# board.net
KiCad netlist of a schematic drawn in EAGLE
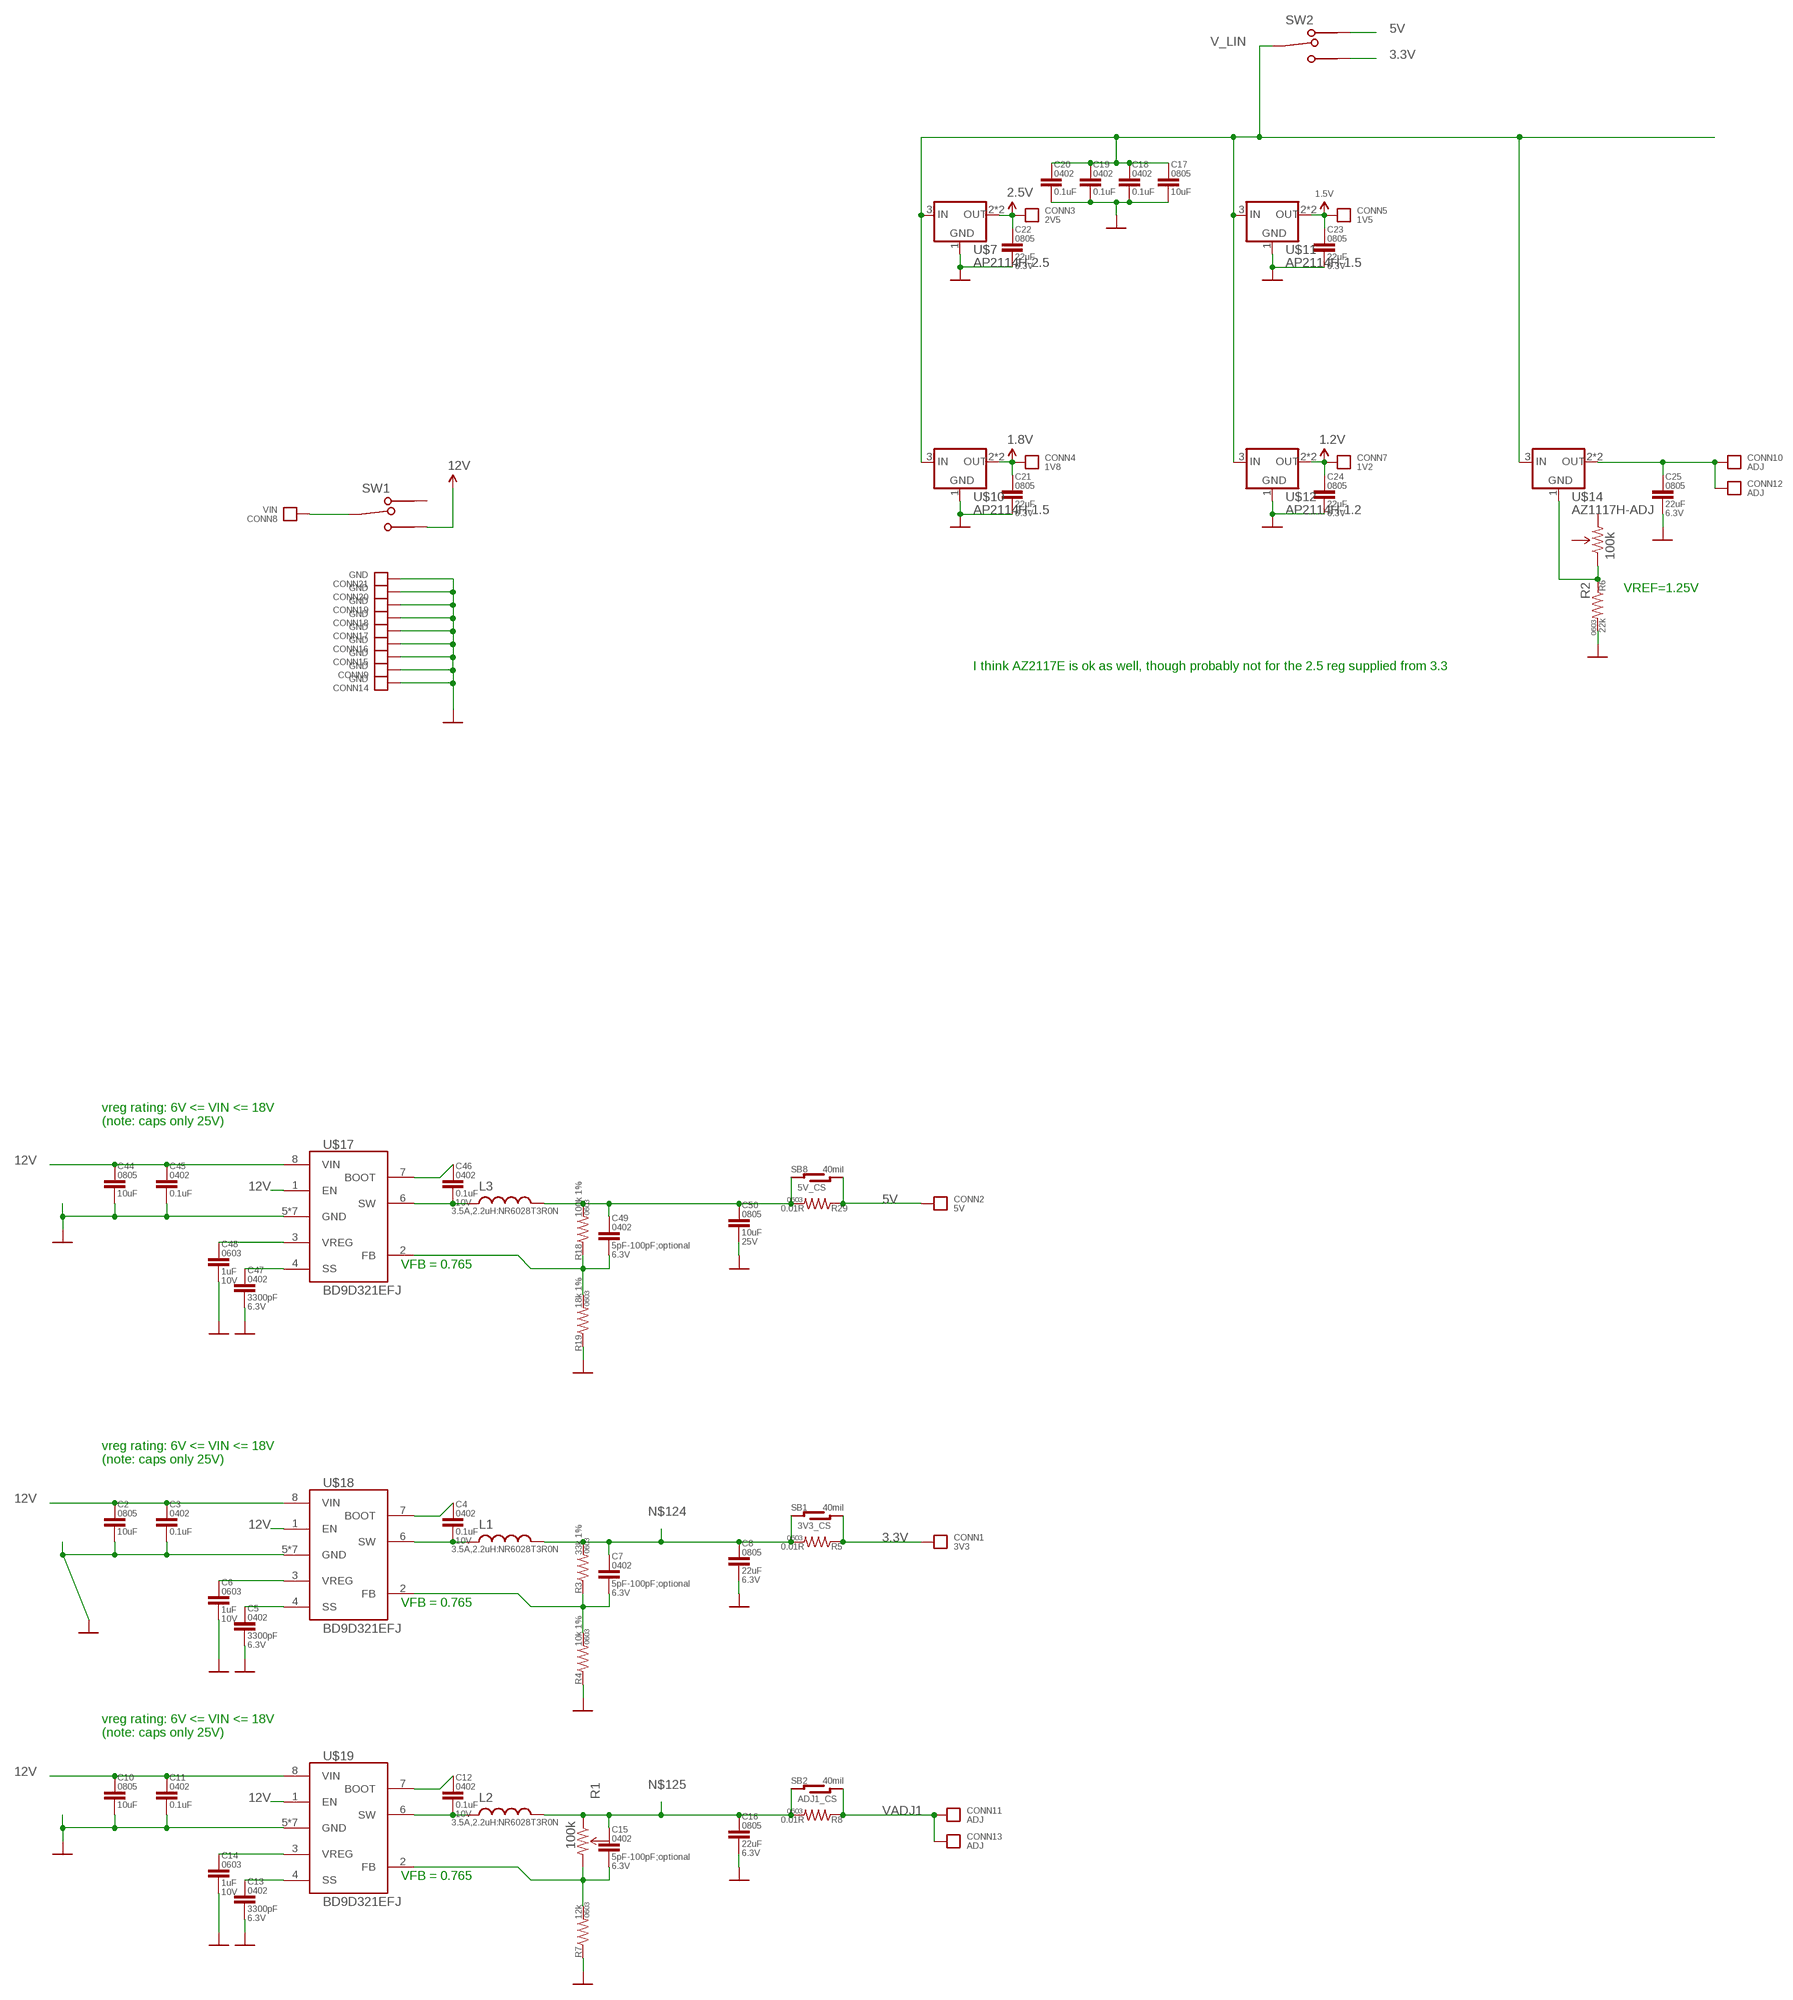
[diagram p0: schematic, sheet 1]

(export (version "E")
  (design (tool "Eeschema 10.0.6"))
  (components
    (comp (ref "C2")
      (value "10uF")
      (footprint "eagle-import:0805-CAP")
      (fields (field (name "VOLTAGE") "6.3V") (field (name "VOLTAGE_1") "25V"))
      (libsource (lib "eagle-import") (part "CAP0805"))
    )
    (comp (ref "C3")
      (value "0.1uF")
      (footprint "eagle-import:0402-CAP")
      (fields (field (name "VOLTAGE") "6.3V") (field (name "VOLTAGE_1") "25V"))
      (libsource (lib "eagle-import") (part "CAP0402-CAP"))
    )
    (comp (ref "C4")
      (value "0.1uF")
      (footprint "eagle-import:0402-CAP")
      (fields (field (name "VOLTAGE") "6.3V") (field (name "VOLTAGE_1") "10V"))
      (libsource (lib "eagle-import") (part "CAP0402-CAP"))
    )
    (comp (ref "C5")
      (value "3300pF")
      (footprint "eagle-import:0402-CAP")
      (fields (field (name "VOLTAGE") "6.3V"))
      (libsource (lib "eagle-import") (part "CAP0402-CAP"))
    )
    (comp (ref "C6")
      (value "1uF")
      (footprint "eagle-import:0603-CAP")
      (fields (field (name "VOLTAGE") "6.3V") (field (name "VOLTAGE_1") "10V"))
      (libsource (lib "eagle-import") (part "CAP0603"))
    )
    (comp (ref "C7")
      (value "5pF-100pF;optional")
      (footprint "eagle-import:0402-CAP")
      (fields (field (name "VOLTAGE") "6.3V"))
      (libsource (lib "eagle-import") (part "CAP0402-CAP"))
    )
    (comp (ref "C8")
      (value "22uF")
      (footprint "eagle-import:0805-CAP")
      (fields (field (name "VOLTAGE") "6.3V"))
      (libsource (lib "eagle-import") (part "CAP0805"))
    )
    (comp (ref "C10")
      (value "10uF")
      (footprint "eagle-import:0805-CAP")
      (fields (field (name "VOLTAGE") "6.3V") (field (name "VOLTAGE_1") "25V"))
      (libsource (lib "eagle-import") (part "CAP0805"))
    )
    (comp (ref "C11")
      (value "0.1uF")
      (footprint "eagle-import:0402-CAP")
      (fields (field (name "VOLTAGE") "6.3V") (field (name "VOLTAGE_1") "25V"))
      (libsource (lib "eagle-import") (part "CAP0402-CAP"))
    )
    (comp (ref "C12")
      (value "0.1uF")
      (footprint "eagle-import:0402-CAP")
      (fields (field (name "VOLTAGE") "6.3V") (field (name "VOLTAGE_1") "10V"))
      (libsource (lib "eagle-import") (part "CAP0402-CAP"))
    )
    (comp (ref "C13")
      (value "3300pF")
      (footprint "eagle-import:0402-CAP")
      (fields (field (name "VOLTAGE") "6.3V"))
      (libsource (lib "eagle-import") (part "CAP0402-CAP"))
    )
    (comp (ref "C14")
      (value "1uF")
      (footprint "eagle-import:0603-CAP")
      (fields (field (name "VOLTAGE") "6.3V") (field (name "VOLTAGE_1") "10V"))
      (libsource (lib "eagle-import") (part "CAP0603"))
    )
    (comp (ref "C15")
      (value "5pF-100pF;optional")
      (footprint "eagle-import:0402-CAP")
      (fields (field (name "VOLTAGE") "6.3V"))
      (libsource (lib "eagle-import") (part "CAP0402-CAP"))
    )
    (comp (ref "C16")
      (value "22uF")
      (footprint "eagle-import:0805-CAP")
      (fields (field (name "VOLTAGE") "6.3V"))
      (libsource (lib "eagle-import") (part "CAP0805"))
    )
    (comp (ref "C17")
      (value "10uF")
      (footprint "eagle-import:0805-CAP")
      (fields (field (name "VOLTAGE") "6.3V") (field (name "VOLTAGE_1") "25V"))
      (libsource (lib "eagle-import") (part "CAP0805"))
    )
    (comp (ref "C18")
      (value "0.1uF")
      (footprint "eagle-import:0402-CAP")
      (fields (field (name "VOLTAGE") "6.3V") (field (name "VOLTAGE_1") "25V"))
      (libsource (lib "eagle-import") (part "CAP0402-CAP"))
    )
    (comp (ref "C19")
      (value "0.1uF")
      (footprint "eagle-import:0402-CAP")
      (fields (field (name "VOLTAGE") "6.3V") (field (name "VOLTAGE_1") "25V"))
      (libsource (lib "eagle-import") (part "CAP0402-CAP"))
    )
    (comp (ref "C20")
      (value "0.1uF")
      (footprint "eagle-import:0402-CAP")
      (fields (field (name "VOLTAGE") "6.3V") (field (name "VOLTAGE_1") "25V"))
      (libsource (lib "eagle-import") (part "CAP0402-CAP"))
    )
    (comp (ref "C21")
      (value "22uF")
      (footprint "eagle-import:0805-CAP")
      (fields (field (name "VOLTAGE") "6.3V"))
      (libsource (lib "eagle-import") (part "CAP0805"))
    )
    (comp (ref "C22")
      (value "22uF")
      (footprint "eagle-import:0805-CAP")
      (fields (field (name "VOLTAGE") "6.3V"))
      (libsource (lib "eagle-import") (part "CAP0805"))
    )
    (comp (ref "C23")
      (value "22uF")
      (footprint "eagle-import:0805-CAP")
      (fields (field (name "VOLTAGE") "6.3V"))
      (libsource (lib "eagle-import") (part "CAP0805"))
    )
    (comp (ref "C24")
      (value "22uF")
      (footprint "eagle-import:0805-CAP")
      (fields (field (name "VOLTAGE") "6.3V"))
      (libsource (lib "eagle-import") (part "CAP0805"))
    )
    (comp (ref "C25")
      (value "22uF")
      (footprint "eagle-import:0805-CAP")
      (fields (field (name "VOLTAGE") "6.3V"))
      (libsource (lib "eagle-import") (part "CAP0805"))
    )
    (comp (ref "C44")
      (value "10uF")
      (footprint "eagle-import:0805-CAP")
      (fields (field (name "VOLTAGE") "6.3V") (field (name "VOLTAGE_1") "25V"))
      (libsource (lib "eagle-import") (part "CAP0805"))
    )
    (comp (ref "C45")
      (value "0.1uF")
      (footprint "eagle-import:0402-CAP")
      (fields (field (name "VOLTAGE") "6.3V") (field (name "VOLTAGE_1") "25V"))
      (libsource (lib "eagle-import") (part "CAP0402-CAP"))
    )
    (comp (ref "C46")
      (value "0.1uF")
      (footprint "eagle-import:0402-CAP")
      (fields (field (name "VOLTAGE") "6.3V") (field (name "VOLTAGE_1") "10V"))
      (libsource (lib "eagle-import") (part "CAP0402-CAP"))
    )
    (comp (ref "C47")
      (value "3300pF")
      (footprint "eagle-import:0402-CAP")
      (fields (field (name "VOLTAGE") "6.3V"))
      (libsource (lib "eagle-import") (part "CAP0402-CAP"))
    )
    (comp (ref "C48")
      (value "1uF")
      (footprint "eagle-import:0603-CAP")
      (fields (field (name "VOLTAGE") "6.3V") (field (name "VOLTAGE_1") "10V"))
      (libsource (lib "eagle-import") (part "CAP0603"))
    )
    (comp (ref "C49")
      (value "5pF-100pF;optional")
      (footprint "eagle-import:0402-CAP")
      (fields (field (name "VOLTAGE") "6.3V"))
      (libsource (lib "eagle-import") (part "CAP0402-CAP"))
    )
    (comp (ref "C50")
      (value "10uF")
      (footprint "eagle-import:0805-CAP")
      (fields (field (name "VOLTAGE") "6.3V") (field (name "VOLTAGE_1") "25V"))
      (libsource (lib "eagle-import") (part "CAP0805"))
    )
    (comp (ref "CONN1")
      (value "3V3")
      (footprint "eagle-import:HOLE_22AWG")
      (libsource (lib "eagle-import") (part "CONNECTOR22AWG"))
    )
    (comp (ref "CONN2")
      (value "5V")
      (footprint "eagle-import:HOLE_22AWG")
      (libsource (lib "eagle-import") (part "CONNECTOR22AWG"))
    )
    (comp (ref "CONN3")
      (value "2V5")
      (footprint "eagle-import:HOLE_22AWG")
      (libsource (lib "eagle-import") (part "CONNECTOR22AWG"))
    )
    (comp (ref "CONN4")
      (value "1V8")
      (footprint "eagle-import:HOLE_22AWG")
      (libsource (lib "eagle-import") (part "CONNECTOR22AWG"))
    )
    (comp (ref "CONN5")
      (value "1V5")
      (footprint "eagle-import:HOLE_22AWG")
      (libsource (lib "eagle-import") (part "CONNECTOR22AWG"))
    )
    (comp (ref "CONN7")
      (value "1V2")
      (footprint "eagle-import:HOLE_22AWG")
      (libsource (lib "eagle-import") (part "CONNECTOR22AWG"))
    )
    (comp (ref "CONN8")
      (value "VIN")
      (footprint "eagle-import:HOLE_22AWG")
      (libsource (lib "eagle-import") (part "CONNECTOR22AWG"))
    )
    (comp (ref "CONN9")
      (value "GND")
      (footprint "eagle-import:HOLE_22AWG")
      (libsource (lib "eagle-import") (part "CONNECTOR22AWG"))
    )
    (comp (ref "CONN10")
      (value "ADJ")
      (footprint "eagle-import:HOLE_22AWG")
      (libsource (lib "eagle-import") (part "CONNECTOR22AWG"))
    )
    (comp (ref "CONN11")
      (value "ADJ")
      (footprint "eagle-import:HOLE_22AWG")
      (libsource (lib "eagle-import") (part "CONNECTOR22AWG"))
    )
    (comp (ref "CONN12")
      (value "ADJ")
      (footprint "eagle-import:HOLE_28AWG")
      (libsource (lib "eagle-import") (part "CONNECTOR28AWG"))
    )
    (comp (ref "CONN13")
      (value "ADJ")
      (footprint "eagle-import:HOLE_28AWG")
      (libsource (lib "eagle-import") (part "CONNECTOR28AWG"))
    )
    (comp (ref "CONN14")
      (value "GND")
      (footprint "eagle-import:HOLE_22AWG")
      (libsource (lib "eagle-import") (part "CONNECTOR22AWG"))
    )
    (comp (ref "CONN15")
      (value "GND")
      (footprint "eagle-import:HOLE_22AWG")
      (libsource (lib "eagle-import") (part "CONNECTOR22AWG"))
    )
    (comp (ref "CONN16")
      (value "GND")
      (footprint "eagle-import:HOLE_22AWG")
      (libsource (lib "eagle-import") (part "CONNECTOR22AWG"))
    )
    (comp (ref "CONN17")
      (value "GND")
      (footprint "eagle-import:HOLE_22AWG")
      (libsource (lib "eagle-import") (part "CONNECTOR22AWG"))
    )
    (comp (ref "CONN18")
      (value "GND")
      (footprint "eagle-import:HOLE_22AWG")
      (libsource (lib "eagle-import") (part "CONNECTOR22AWG"))
    )
    (comp (ref "CONN19")
      (value "GND")
      (footprint "eagle-import:HOLE_22AWG")
      (libsource (lib "eagle-import") (part "CONNECTOR22AWG"))
    )
    (comp (ref "CONN20")
      (value "GND")
      (footprint "eagle-import:HOLE_22AWG")
      (libsource (lib "eagle-import") (part "CONNECTOR22AWG"))
    )
    (comp (ref "CONN21")
      (value "GND")
      (footprint "eagle-import:HOLE_22AWG")
      (libsource (lib "eagle-import") (part "CONNECTOR22AWG"))
    )
    (comp (ref "L1")
      (value "3.5A,2.2uH:NR6028T3R0N")
      (footprint "eagle-import:NR60XX")
      (libsource (lib "eagle-import") (part "INDUCTORNR60XX"))
    )
    (comp (ref "L2")
      (value "3.5A,2.2uH:NR6028T3R0N")
      (footprint "eagle-import:NR60XX")
      (libsource (lib "eagle-import") (part "INDUCTORNR60XX"))
    )
    (comp (ref "L3")
      (value "3.5A,2.2uH:NR6028T3R0N")
      (footprint "eagle-import:NR60XX")
      (libsource (lib "eagle-import") (part "INDUCTORNR60XX"))
    )
    (comp (ref "R1")
      (value "100k")
      (footprint "eagle-import:TRIM_POT_PTH")
      (libsource (lib "eagle-import") (part "TRIMPOTPTH"))
    )
    (comp (ref "R2")
      (value "100k")
      (footprint "eagle-import:TRIM_POT_PTH")
      (libsource (lib "eagle-import") (part "TRIMPOTPTH"))
    )
    (comp (ref "R3")
      (value "33k 1%")
      (footprint "eagle-import:0603-RES")
      (libsource (lib "eagle-import") (part "RESISTOR0603"))
    )
    (comp (ref "R4")
      (value "10k 1%")
      (footprint "eagle-import:0603-RES")
      (libsource (lib "eagle-import") (part "RESISTOR0603"))
    )
    (comp (ref "R5")
      (value "0.01R")
      (footprint "eagle-import:0603-RES")
      (libsource (lib "eagle-import") (part "RESISTOR0603"))
    )
    (comp (ref "R6")
      (value "22k")
      (footprint "eagle-import:0603-RES")
      (libsource (lib "eagle-import") (part "RESISTOR0603"))
    )
    (comp (ref "R7")
      (value "12k")
      (footprint "eagle-import:0603-RES")
      (libsource (lib "eagle-import") (part "RESISTOR0603"))
    )
    (comp (ref "R8")
      (value "0.01R")
      (footprint "eagle-import:0603-RES")
      (libsource (lib "eagle-import") (part "RESISTOR0603"))
    )
    (comp (ref "R18")
      (value "100k 1%")
      (footprint "eagle-import:0603-RES")
      (libsource (lib "eagle-import") (part "RESISTOR0603"))
    )
    (comp (ref "R19")
      (value "18k 1%")
      (footprint "eagle-import:0603-RES")
      (libsource (lib "eagle-import") (part "RESISTOR0603"))
    )
    (comp (ref "R29")
      (value "0.01R")
      (footprint "eagle-import:0603-RES")
      (libsource (lib "eagle-import") (part "RESISTOR0603"))
    )
    (comp (ref "SB1")
      (value "3V3_CS")
      (footprint "eagle-import:SOLDER-BRIDGE-OPEN-LARGE")
      (libsource (lib "eagle-import") (part "SOLDER-BRIDGEOPEN-WIDE"))
    )
    (comp (ref "SB2")
      (value "ADJ1_CS")
      (footprint "eagle-import:SOLDER-BRIDGE-OPEN-LARGE")
      (libsource (lib "eagle-import") (part "SOLDER-BRIDGEOPEN-WIDE"))
    )
    (comp (ref "SB8")
      (value "5V_CS")
      (footprint "eagle-import:SOLDER-BRIDGE-OPEN-LARGE")
      (libsource (lib "eagle-import") (part "SOLDER-BRIDGEOPEN-WIDE"))
    )
    (comp (ref "SW1")
      (value "SWITCH_SPDT")
      (footprint "eagle-import:SWITCH_SLIDE_SPDT")
      (libsource (lib "eagle-import") (part "SWITCH_SPDT"))
    )
    (comp (ref "SW2")
      (value "SWITCH_SPDT")
      (footprint "eagle-import:SWITCH_SLIDE_SPDT")
      (libsource (lib "eagle-import") (part "SWITCH_SPDT"))
    )
    (comp (ref "U$7")
      (value "AP2114H-2.5")
      (footprint "eagle-import:SOT223")
      (libsource (lib "eagle-import") (part "VREGSOT223"))
    )
    (comp (ref "U$10")
      (value "AP2114H-1.5")
      (footprint "eagle-import:SOT223")
      (libsource (lib "eagle-import") (part "VREGSOT223"))
    )
    (comp (ref "U$11")
      (value "AP2114H-1.5")
      (footprint "eagle-import:SOT223")
      (libsource (lib "eagle-import") (part "VREGSOT223"))
    )
    (comp (ref "U$12")
      (value "AP2114H-1.2")
      (footprint "eagle-import:SOT223")
      (libsource (lib "eagle-import") (part "VREGSOT223"))
    )
    (comp (ref "U$14")
      (value "AZ1117H-ADJ")
      (footprint "eagle-import:SOT223")
      (libsource (lib "eagle-import") (part "VREGSOT223"))
    )
    (comp (ref "U$17")
      (value "BD9D321EFJ")
      (footprint "eagle-import:HTSOP8")
      (libsource (lib "eagle-import") (part "BD9D321EFJ"))
    )
    (comp (ref "U$18")
      (value "BD9D321EFJ")
      (footprint "eagle-import:HTSOP8")
      (libsource (lib "eagle-import") (part "BD9D321EFJ"))
    )
    (comp (ref "U$19")
      (value "BD9D321EFJ")
      (footprint "eagle-import:HTSOP8")
      (libsource (lib "eagle-import") (part "BD9D321EFJ"))
    )
  )
  (nets
    (net (code "1") (name "/3.3V") (class "Default")
      (node (ref "CONN1") (pin "P") (pinfunction "P_P") (pintype "bidirectional"))
      (node (ref "R5") (pin "1") (pinfunction "1_1") (pintype "passive"))
      (node (ref "SB1") (pin "R1") (pinfunction "P$2_R1") (pintype "passive"))
      (node (ref "SB1") (pin "R2") (pinfunction "P$2_R2") (pintype "passive"))
      (node (ref "SW2") (pin "P2") (pinfunction "P2_P2") (pintype "bidirectional"))
    )
    (net (code "2") (name "/5V") (class "Default")
      (node (ref "CONN2") (pin "P") (pinfunction "P_P") (pintype "bidirectional"))
      (node (ref "R29") (pin "1") (pinfunction "1_1") (pintype "passive"))
      (node (ref "SB8") (pin "R1") (pinfunction "P$2_R1") (pintype "passive"))
      (node (ref "SB8") (pin "R2") (pinfunction "P$2_R2") (pintype "passive"))
      (node (ref "SW2") (pin "P1") (pinfunction "P1_P1") (pintype "bidirectional"))
    )
    (net (code "3") (name "/N$124") (class "Default")
      (node (ref "C7") (pin "1") (pinfunction "1_1") (pintype "passive"))
      (node (ref "C8") (pin "1") (pinfunction "1_1") (pintype "passive"))
      (node (ref "L1") (pin "P$2") (pinfunction "2_P$2") (pintype "passive"))
      (node (ref "R3") (pin "2") (pinfunction "2_2") (pintype "passive"))
      (node (ref "R5") (pin "2") (pinfunction "2_2") (pintype "passive"))
      (node (ref "SB1") (pin "L1") (pinfunction "P$1_L1") (pintype "passive"))
      (node (ref "SB1") (pin "L2") (pinfunction "P$1_L2") (pintype "passive"))
    )
    (net (code "4") (name "/N$125") (class "Default")
      (node (ref "C15") (pin "1") (pinfunction "1_1") (pintype "passive"))
      (node (ref "C16") (pin "1") (pinfunction "1_1") (pintype "passive"))
      (node (ref "L2") (pin "P$2") (pinfunction "2_P$2") (pintype "passive"))
      (node (ref "R1") (pin "1") (pinfunction "CCW_1") (pintype "passive"))
      (node (ref "R8") (pin "2") (pinfunction "2_2") (pintype "passive"))
      (node (ref "SB2") (pin "L1") (pinfunction "P$1_L1") (pintype "passive"))
      (node (ref "SB2") (pin "L2") (pinfunction "P$1_L2") (pintype "passive"))
    )
    (net (code "5") (name "/VADJ1") (class "Default")
      (node (ref "CONN11") (pin "P") (pinfunction "P_P") (pintype "bidirectional"))
      (node (ref "CONN13") (pin "P") (pinfunction "P_P") (pintype "bidirectional"))
      (node (ref "R8") (pin "1") (pinfunction "1_1") (pintype "passive"))
      (node (ref "SB2") (pin "R1") (pinfunction "P$2_R1") (pintype "passive"))
      (node (ref "SB2") (pin "R2") (pinfunction "P$2_R2") (pintype "passive"))
    )
    (net (code "6") (name "/V_LIN") (class "Default")
      (node (ref "C17") (pin "1") (pinfunction "1_1") (pintype "passive"))
      (node (ref "C18") (pin "1") (pinfunction "1_1") (pintype "passive"))
      (node (ref "C19") (pin "1") (pinfunction "1_1") (pintype "passive"))
      (node (ref "C20") (pin "1") (pinfunction "1_1") (pintype "passive"))
      (node (ref "SW2") (pin "C") (pinfunction "C_C") (pintype "bidirectional"))
      (node (ref "U$10") (pin "3") (pinfunction "IN_3") (pintype "input"))
      (node (ref "U$11") (pin "3") (pinfunction "IN_3") (pintype "input"))
      (node (ref "U$12") (pin "3") (pinfunction "IN_3") (pintype "input"))
      (node (ref "U$14") (pin "3") (pinfunction "IN_3") (pintype "input"))
      (node (ref "U$7") (pin "3") (pinfunction "IN_3") (pintype "input"))
    )
    (net (code "7") (name "1.2V") (class "Default")
      (node (ref "C24") (pin "1") (pinfunction "1_1") (pintype "passive"))
      (node (ref "CONN7") (pin "P") (pinfunction "P_P") (pintype "bidirectional"))
      (node (ref "U$12") (pin "2") (pinfunction "OUT_2") (pintype "passive"))
      (node (ref "U$12") (pin "4") (pinfunction "OUT_4") (pintype "passive"))
    )
    (net (code "8") (name "1.5V") (class "Default")
      (node (ref "C23") (pin "1") (pinfunction "1_1") (pintype "passive"))
      (node (ref "CONN5") (pin "P") (pinfunction "P_P") (pintype "bidirectional"))
      (node (ref "U$11") (pin "2") (pinfunction "OUT_2") (pintype "passive"))
      (node (ref "U$11") (pin "4") (pinfunction "OUT_4") (pintype "passive"))
    )
    (net (code "9") (name "1.8V") (class "Default")
      (node (ref "C21") (pin "1") (pinfunction "1_1") (pintype "passive"))
      (node (ref "CONN4") (pin "P") (pinfunction "P_P") (pintype "bidirectional"))
      (node (ref "U$10") (pin "2") (pinfunction "OUT_2") (pintype "passive"))
      (node (ref "U$10") (pin "4") (pinfunction "OUT_4") (pintype "passive"))
    )
    (net (code "10") (name "2.5V") (class "Default")
      (node (ref "C22") (pin "1") (pinfunction "1_1") (pintype "passive"))
      (node (ref "CONN3") (pin "P") (pinfunction "P_P") (pintype "bidirectional"))
      (node (ref "U$7") (pin "2") (pinfunction "OUT_2") (pintype "passive"))
      (node (ref "U$7") (pin "4") (pinfunction "OUT_4") (pintype "passive"))
    )
    (net (code "11") (name "12V") (class "Default")
      (node (ref "C10") (pin "1") (pinfunction "1_1") (pintype "passive"))
      (node (ref "C11") (pin "1") (pinfunction "1_1") (pintype "passive"))
      (node (ref "C2") (pin "1") (pinfunction "1_1") (pintype "passive"))
      (node (ref "C3") (pin "1") (pinfunction "1_1") (pintype "passive"))
      (node (ref "C44") (pin "1") (pinfunction "1_1") (pintype "passive"))
      (node (ref "C45") (pin "1") (pinfunction "1_1") (pintype "passive"))
      (node (ref "SW1") (pin "P2") (pinfunction "P2_P2") (pintype "bidirectional"))
      (node (ref "U$17") (pin "1") (pinfunction "EN_1") (pintype "input"))
      (node (ref "U$17") (pin "8") (pinfunction "VIN_8") (pintype "input"))
      (node (ref "U$18") (pin "1") (pinfunction "EN_1") (pintype "input"))
      (node (ref "U$18") (pin "8") (pinfunction "VIN_8") (pintype "input"))
      (node (ref "U$19") (pin "1") (pinfunction "EN_1") (pintype "input"))
      (node (ref "U$19") (pin "8") (pinfunction "VIN_8") (pintype "input"))
    )
    (net (code "12") (name "GND") (class "Default")
      (node (ref "C10") (pin "2") (pinfunction "2_2") (pintype "passive"))
      (node (ref "C11") (pin "2") (pinfunction "2_2") (pintype "passive"))
      (node (ref "C13") (pin "2") (pinfunction "2_2") (pintype "passive"))
      (node (ref "C14") (pin "2") (pinfunction "2_2") (pintype "passive"))
      (node (ref "C16") (pin "2") (pinfunction "2_2") (pintype "passive"))
      (node (ref "C17") (pin "2") (pinfunction "2_2") (pintype "passive"))
      (node (ref "C18") (pin "2") (pinfunction "2_2") (pintype "passive"))
      (node (ref "C19") (pin "2") (pinfunction "2_2") (pintype "passive"))
      (node (ref "C2") (pin "2") (pinfunction "2_2") (pintype "passive"))
      (node (ref "C20") (pin "2") (pinfunction "2_2") (pintype "passive"))
      (node (ref "C21") (pin "2") (pinfunction "2_2") (pintype "passive"))
      (node (ref "C22") (pin "2") (pinfunction "2_2") (pintype "passive"))
      (node (ref "C23") (pin "2") (pinfunction "2_2") (pintype "passive"))
      (node (ref "C24") (pin "2") (pinfunction "2_2") (pintype "passive"))
      (node (ref "C25") (pin "2") (pinfunction "2_2") (pintype "passive"))
      (node (ref "C3") (pin "2") (pinfunction "2_2") (pintype "passive"))
      (node (ref "C44") (pin "2") (pinfunction "2_2") (pintype "passive"))
      (node (ref "C45") (pin "2") (pinfunction "2_2") (pintype "passive"))
      (node (ref "C47") (pin "2") (pinfunction "2_2") (pintype "passive"))
      (node (ref "C48") (pin "2") (pinfunction "2_2") (pintype "passive"))
      (node (ref "C5") (pin "2") (pinfunction "2_2") (pintype "passive"))
      (node (ref "C50") (pin "2") (pinfunction "2_2") (pintype "passive"))
      (node (ref "C6") (pin "2") (pinfunction "2_2") (pintype "passive"))
      (node (ref "C8") (pin "2") (pinfunction "2_2") (pintype "passive"))
      (node (ref "CONN14") (pin "P") (pinfunction "P_P") (pintype "bidirectional"))
      (node (ref "CONN15") (pin "P") (pinfunction "P_P") (pintype "bidirectional"))
      (node (ref "CONN16") (pin "P") (pinfunction "P_P") (pintype "bidirectional"))
      (node (ref "CONN17") (pin "P") (pinfunction "P_P") (pintype "bidirectional"))
      (node (ref "CONN18") (pin "P") (pinfunction "P_P") (pintype "bidirectional"))
      (node (ref "CONN19") (pin "P") (pinfunction "P_P") (pintype "bidirectional"))
      (node (ref "CONN20") (pin "P") (pinfunction "P_P") (pintype "bidirectional"))
      (node (ref "CONN21") (pin "P") (pinfunction "P_P") (pintype "bidirectional"))
      (node (ref "CONN9") (pin "P") (pinfunction "P_P") (pintype "bidirectional"))
      (node (ref "R19") (pin "1") (pinfunction "1_1") (pintype "passive"))
      (node (ref "R4") (pin "1") (pinfunction "1_1") (pintype "passive"))
      (node (ref "R6") (pin "2") (pinfunction "2_2") (pintype "passive"))
      (node (ref "R7") (pin "1") (pinfunction "1_1") (pintype "passive"))
      (node (ref "U$10") (pin "1") (pinfunction "GND_1") (pintype "input"))
      (node (ref "U$11") (pin "1") (pinfunction "GND_1") (pintype "input"))
      (node (ref "U$12") (pin "1") (pinfunction "GND_1") (pintype "input"))
      (node (ref "U$17") (pin "5") (pinfunction "GND_5") (pintype "input"))
      (node (ref "U$17") (pin "P$1") (pinfunction "GND_P$1") (pintype "input"))
      (node (ref "U$17") (pin "P$2") (pinfunction "GND_P$2") (pintype "input"))
      (node (ref "U$17") (pin "P$3") (pinfunction "GND_P$3") (pintype "input"))
      (node (ref "U$17") (pin "P$4") (pinfunction "GND_P$4") (pintype "input"))
      (node (ref "U$17") (pin "P$5") (pinfunction "GND_P$5") (pintype "input"))
      (node (ref "U$17") (pin "PAD") (pinfunction "GND_PAD") (pintype "input"))
      (node (ref "U$18") (pin "5") (pinfunction "GND_5") (pintype "input"))
      (node (ref "U$18") (pin "P$1") (pinfunction "GND_P$1") (pintype "input"))
      (node (ref "U$18") (pin "P$2") (pinfunction "GND_P$2") (pintype "input"))
      (node (ref "U$18") (pin "P$3") (pinfunction "GND_P$3") (pintype "input"))
      (node (ref "U$18") (pin "P$4") (pinfunction "GND_P$4") (pintype "input"))
      (node (ref "U$18") (pin "P$5") (pinfunction "GND_P$5") (pintype "input"))
      (node (ref "U$18") (pin "PAD") (pinfunction "GND_PAD") (pintype "input"))
      (node (ref "U$19") (pin "5") (pinfunction "GND_5") (pintype "input"))
      (node (ref "U$19") (pin "P$1") (pinfunction "GND_P$1") (pintype "input"))
      (node (ref "U$19") (pin "P$2") (pinfunction "GND_P$2") (pintype "input"))
      (node (ref "U$19") (pin "P$3") (pinfunction "GND_P$3") (pintype "input"))
      (node (ref "U$19") (pin "P$4") (pinfunction "GND_P$4") (pintype "input"))
      (node (ref "U$19") (pin "P$5") (pinfunction "GND_P$5") (pintype "input"))
      (node (ref "U$19") (pin "PAD") (pinfunction "GND_PAD") (pintype "input"))
      (node (ref "U$7") (pin "1") (pinfunction "GND_1") (pintype "input"))
    )
    (net (code "13") (name "Net-(C25-Pad1)") (class "Default")
      (node (ref "C25") (pin "1") (pinfunction "1_1") (pintype "passive"))
      (node (ref "CONN10") (pin "P") (pinfunction "P_P") (pintype "bidirectional"))
      (node (ref "CONN12") (pin "P") (pinfunction "P_P") (pintype "bidirectional"))
      (node (ref "U$14") (pin "2") (pinfunction "OUT_2") (pintype "passive"))
      (node (ref "U$14") (pin "4") (pinfunction "OUT_4") (pintype "passive"))
    )
    (net (code "14") (name "Net-(CONN8-PadP)") (class "Default")
      (node (ref "CONN8") (pin "P") (pinfunction "P_P") (pintype "bidirectional"))
      (node (ref "SW1") (pin "C") (pinfunction "C_C") (pintype "bidirectional"))
    )
    (net (code "15") (name "Net-(L1-1)") (class "Default")
      (node (ref "C4") (pin "2") (pinfunction "2_2") (pintype "passive"))
      (node (ref "L1") (pin "P$1") (pinfunction "1_P$1") (pintype "passive"))
      (node (ref "U$18") (pin "6") (pinfunction "SW_6") (pintype "input"))
    )
    (net (code "16") (name "Net-(L2-1)") (class "Default")
      (node (ref "C12") (pin "2") (pinfunction "2_2") (pintype "passive"))
      (node (ref "L2") (pin "P$1") (pinfunction "1_P$1") (pintype "passive"))
      (node (ref "U$19") (pin "6") (pinfunction "SW_6") (pintype "input"))
    )
    (net (code "17") (name "Net-(L3-1)") (class "Default")
      (node (ref "C46") (pin "2") (pinfunction "2_2") (pintype "passive"))
      (node (ref "L3") (pin "P$1") (pinfunction "1_P$1") (pintype "passive"))
      (node (ref "U$17") (pin "6") (pinfunction "SW_6") (pintype "input"))
    )
    (net (code "18") (name "Net-(L3-2)") (class "Default")
      (node (ref "C49") (pin "1") (pinfunction "1_1") (pintype "passive"))
      (node (ref "C50") (pin "1") (pinfunction "1_1") (pintype "passive"))
      (node (ref "L3") (pin "P$2") (pinfunction "2_P$2") (pintype "passive"))
      (node (ref "R18") (pin "2") (pinfunction "2_2") (pintype "passive"))
      (node (ref "R29") (pin "2") (pinfunction "2_2") (pintype "passive"))
      (node (ref "SB8") (pin "L1") (pinfunction "P$1_L1") (pintype "passive"))
      (node (ref "SB8") (pin "L2") (pinfunction "P$1_L2") (pintype "passive"))
    )
    (net (code "19") (name "Net-(R1-CW)") (class "Default")
      (node (ref "C15") (pin "2") (pinfunction "2_2") (pintype "passive"))
      (node (ref "R1") (pin "3") (pinfunction "CW_3") (pintype "passive"))
      (node (ref "R7") (pin "2") (pinfunction "2_2") (pintype "passive"))
      (node (ref "U$19") (pin "2") (pinfunction "FB_2") (pintype "input"))
    )
    (net (code "20") (name "Net-(R2-CCW)") (class "Default")
      (node (ref "R2") (pin "1") (pinfunction "CCW_1") (pintype "passive"))
      (node (ref "R6") (pin "1") (pinfunction "1_1") (pintype "passive"))
      (node (ref "U$14") (pin "1") (pinfunction "GND_1") (pintype "input"))
    )
    (net (code "21") (name "Net-(U$17-BOOT)") (class "Default")
      (node (ref "C46") (pin "1") (pinfunction "1_1") (pintype "passive"))
      (node (ref "U$17") (pin "7") (pinfunction "BOOT_7") (pintype "input"))
    )
    (net (code "22") (name "Net-(U$17-FB)") (class "Default")
      (node (ref "C49") (pin "2") (pinfunction "2_2") (pintype "passive"))
      (node (ref "R18") (pin "1") (pinfunction "1_1") (pintype "passive"))
      (node (ref "R19") (pin "2") (pinfunction "2_2") (pintype "passive"))
      (node (ref "U$17") (pin "2") (pinfunction "FB_2") (pintype "input"))
    )
    (net (code "23") (name "Net-(U$17-SS)") (class "Default")
      (node (ref "C47") (pin "1") (pinfunction "1_1") (pintype "passive"))
      (node (ref "U$17") (pin "4") (pinfunction "SS_4") (pintype "input"))
    )
    (net (code "24") (name "Net-(U$17-VREG)") (class "Default")
      (node (ref "C48") (pin "1") (pinfunction "1_1") (pintype "passive"))
      (node (ref "U$17") (pin "3") (pinfunction "VREG_3") (pintype "input"))
    )
    (net (code "25") (name "Net-(U$18-BOOT)") (class "Default")
      (node (ref "C4") (pin "1") (pinfunction "1_1") (pintype "passive"))
      (node (ref "U$18") (pin "7") (pinfunction "BOOT_7") (pintype "input"))
    )
    (net (code "26") (name "Net-(U$18-FB)") (class "Default")
      (node (ref "C7") (pin "2") (pinfunction "2_2") (pintype "passive"))
      (node (ref "R3") (pin "1") (pinfunction "1_1") (pintype "passive"))
      (node (ref "R4") (pin "2") (pinfunction "2_2") (pintype "passive"))
      (node (ref "U$18") (pin "2") (pinfunction "FB_2") (pintype "input"))
    )
    (net (code "27") (name "Net-(U$18-SS)") (class "Default")
      (node (ref "C5") (pin "1") (pinfunction "1_1") (pintype "passive"))
      (node (ref "U$18") (pin "4") (pinfunction "SS_4") (pintype "input"))
    )
    (net (code "28") (name "Net-(U$18-VREG)") (class "Default")
      (node (ref "C6") (pin "1") (pinfunction "1_1") (pintype "passive"))
      (node (ref "U$18") (pin "3") (pinfunction "VREG_3") (pintype "input"))
    )
    (net (code "29") (name "Net-(U$19-BOOT)") (class "Default")
      (node (ref "C12") (pin "1") (pinfunction "1_1") (pintype "passive"))
      (node (ref "U$19") (pin "7") (pinfunction "BOOT_7") (pintype "input"))
    )
    (net (code "30") (name "Net-(U$19-SS)") (class "Default")
      (node (ref "C13") (pin "1") (pinfunction "1_1") (pintype "passive"))
      (node (ref "U$19") (pin "4") (pinfunction "SS_4") (pintype "input"))
    )
    (net (code "31") (name "Net-(U$19-VREG)") (class "Default")
      (node (ref "C14") (pin "1") (pinfunction "1_1") (pintype "passive"))
      (node (ref "U$19") (pin "3") (pinfunction "VREG_3") (pintype "input"))
    )
    (net (code "32") (name "unconnected-(R1-WIPER-Pad2)") (class "Default")
      (node (ref "R1") (pin "2") (pinfunction "WIPER_2") (pintype "passive"))
    )
    (net (code "33") (name "unconnected-(R2-CW-Pad3)") (class "Default")
      (node (ref "R2") (pin "3") (pinfunction "CW_3") (pintype "passive"))
    )
    (net (code "34") (name "unconnected-(R2-WIPER-Pad2)") (class "Default")
      (node (ref "R2") (pin "2") (pinfunction "WIPER_2") (pintype "passive"))
    )
    (net (code "35") (name "unconnected-(SW1-PadP1)") (class "Default")
      (node (ref "SW1") (pin "P1") (pinfunction "P1_P1") (pintype "bidirectional"))
    )
  )
)
